# sonopi-dac-type2.net
KiCad netlist of a schematic drawn in EAGLE
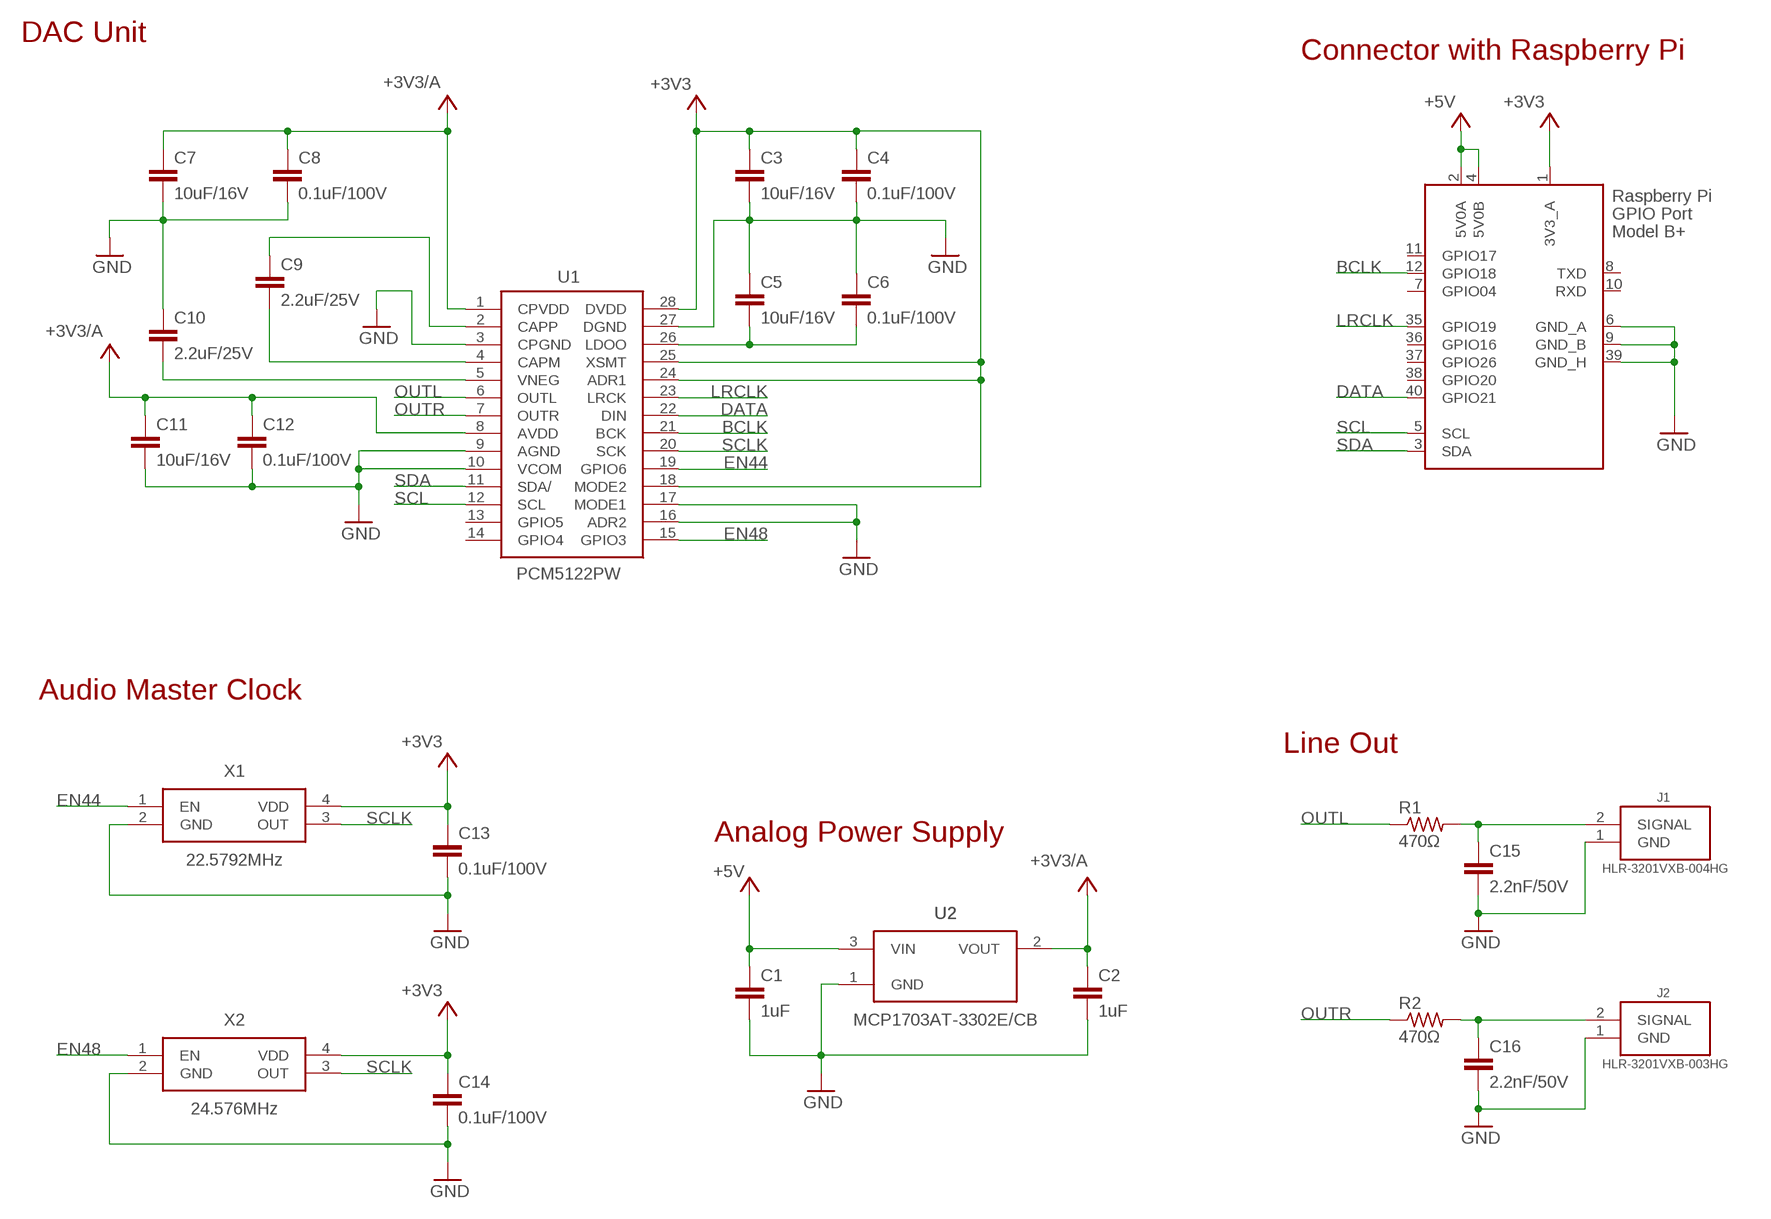
[diagram p0: schematic, sheet 1]

(export (version "E")
  (design (tool "Eeschema 10.0.6"))
  (components
    (comp (ref "C1")
      (value "1uF")
      (footprint "eagle-import:C0603")
      (libsource (lib "eagle-import") (part "C-EUC0603"))
    )
    (comp (ref "C2")
      (value "1uF")
      (footprint "eagle-import:C0603")
      (libsource (lib "eagle-import") (part "C-EUC0603"))
    )
    (comp (ref "C3")
      (value "10uF/16V")
      (footprint "eagle-import:C3216")
      (libsource (lib "eagle-import") (part "C-EUC3216"))
    )
    (comp (ref "C4")
      (value "0.1uF/100V")
      (footprint "eagle-import:C0603")
      (libsource (lib "eagle-import") (part "C-EUC0603"))
    )
    (comp (ref "C5")
      (value "10uF/16V")
      (footprint "eagle-import:C3216")
      (libsource (lib "eagle-import") (part "C-EUC3216"))
    )
    (comp (ref "C6")
      (value "0.1uF/100V")
      (footprint "eagle-import:C0603")
      (libsource (lib "eagle-import") (part "C-EUC0603"))
    )
    (comp (ref "C7")
      (value "10uF/16V")
      (footprint "eagle-import:C3216")
      (libsource (lib "eagle-import") (part "C-EUC3216"))
    )
    (comp (ref "C8")
      (value "0.1uF/100V")
      (footprint "eagle-import:C0603")
      (libsource (lib "eagle-import") (part "C-EUC0603"))
    )
    (comp (ref "C9")
      (value "2.2uF/25V")
      (footprint "eagle-import:C0805")
      (libsource (lib "eagle-import") (part "C-EUC0805"))
    )
    (comp (ref "C10")
      (value "2.2uF/25V")
      (footprint "eagle-import:C0805")
      (libsource (lib "eagle-import") (part "C-EUC0805"))
    )
    (comp (ref "C11")
      (value "10uF/16V")
      (footprint "eagle-import:C3216")
      (libsource (lib "eagle-import") (part "C-EUC3216"))
    )
    (comp (ref "C12")
      (value "0.1uF/100V")
      (footprint "eagle-import:C0603")
      (libsource (lib "eagle-import") (part "C-EUC0603"))
    )
    (comp (ref "C13")
      (value "0.1uF/100V")
      (footprint "eagle-import:C0603")
      (libsource (lib "eagle-import") (part "C-EUC0603"))
    )
    (comp (ref "C14")
      (value "0.1uF/100V")
      (footprint "eagle-import:C0603")
      (libsource (lib "eagle-import") (part "C-EUC0603"))
    )
    (comp (ref "C15")
      (value "2.2nF/50V")
      (footprint "eagle-import:C0603")
      (libsource (lib "eagle-import") (part "C-EUC0603"))
    )
    (comp (ref "C16")
      (value "2.2nF/50V")
      (footprint "eagle-import:C0603")
      (libsource (lib "eagle-import") (part "C-EUC0603"))
    )
    (comp (ref "J1")
      (value "HLR-3201VXB-004HG")
      (footprint "eagle-import:HLR-3201VXB")
      (libsource (lib "eagle-import") (part "1CH-RCA-HLR-3201VXB"))
    )
    (comp (ref "J2")
      (value "HLR-3201VXB-003HG")
      (footprint "eagle-import:HLR-3201VXB")
      (libsource (lib "eagle-import") (part "1CH-RCA-HLR-3201VXB"))
    )
    (comp (ref "J3")
      (value "RASPI_BOARD_B+#_ZERO")
      (footprint "eagle-import:RASPI_BOARD_B+HAT_ZERO")
      (libsource (lib "eagle-import") (part "RASPI_BOARD_B+#_ZERO"))
    )
    (comp (ref "R1")
      (value "470Ω")
      (footprint "eagle-import:R0603")
      (libsource (lib "eagle-import") (part "R-US_R0603"))
    )
    (comp (ref "R2")
      (value "470Ω")
      (footprint "eagle-import:R0603")
      (libsource (lib "eagle-import") (part "R-US_R0603"))
    )
    (comp (ref "U1")
      (value "PCM5122PW")
      (footprint "eagle-import:SOP65P640X120-28N")
      (fields (field (name "MOUSER_PART_NUMBER") "595-PCM5122PW") (field (name "RS_PART_NUMBER") "8143732P"))
      (libsource (lib "eagle-import") (part "PCM5122PW"))
    )
    (comp (ref "U2")
      (value "MCP1703AT-3302E/CB")
      (footprint "eagle-import:SOT23")
      (libsource (lib "eagle-import") (part "LDO-REGULATOR"))
    )
    (comp (ref "X1")
      (value "22.5792MHz")
      (footprint "eagle-import:3225-SMD-HS")
      (libsource (lib "eagle-import") (part "OSC-3225HS"))
    )
    (comp (ref "X2")
      (value "24.576MHz")
      (footprint "eagle-import:3225-SMD-HS")
      (libsource (lib "eagle-import") (part "OSC-3225HS"))
    )
  )
  (nets
    (net (code "1") (name "+3V3") (class "Default")
      (node (ref "C13") (pin "1") (pinfunction "1_1") (pintype "passive"))
      (node (ref "C14") (pin "1") (pinfunction "1_1") (pintype "passive"))
      (node (ref "C3") (pin "1") (pinfunction "1_1") (pintype "passive"))
      (node (ref "C4") (pin "1") (pinfunction "1_1") (pintype "passive"))
      (node (ref "J3") (pin "1") (pinfunction "3V3_A_1") (pintype "power_in"))
      (node (ref "U1") (pin "18") (pinfunction "MODE2_18") (pintype "bidirectional"))
      (node (ref "U1") (pin "24") (pinfunction "ADR1_24") (pintype "bidirectional"))
      (node (ref "U1") (pin "25") (pinfunction "XSMT_25") (pintype "bidirectional"))
      (node (ref "U1") (pin "28") (pinfunction "DVDD_28") (pintype "bidirectional"))
      (node (ref "X1") (pin "4") (pinfunction "VDD_4") (pintype "power_in"))
      (node (ref "X2") (pin "4") (pinfunction "VDD_4") (pintype "power_in"))
    )
    (net (code "2") (name "+3V3{slash}A") (class "Default")
      (node (ref "C11") (pin "1") (pinfunction "1_1") (pintype "passive"))
      (node (ref "C12") (pin "1") (pinfunction "1_1") (pintype "passive"))
      (node (ref "C2") (pin "1") (pinfunction "1_1") (pintype "passive"))
      (node (ref "C7") (pin "1") (pinfunction "1_1") (pintype "passive"))
      (node (ref "C8") (pin "1") (pinfunction "1_1") (pintype "passive"))
      (node (ref "U1") (pin "1") (pinfunction "CPVDD_1") (pintype "bidirectional"))
      (node (ref "U1") (pin "8") (pinfunction "AVDD_8") (pintype "bidirectional"))
      (node (ref "U2") (pin "2") (pinfunction "VOUT_2") (pintype "bidirectional"))
    )
    (net (code "3") (name "+5V") (class "Default")
      (node (ref "C1") (pin "1") (pinfunction "1_1") (pintype "passive"))
      (node (ref "J3") (pin "2") (pinfunction "5V0A_2") (pintype "power_in"))
      (node (ref "J3") (pin "4") (pinfunction "5V0B_4") (pintype "power_in"))
      (node (ref "U2") (pin "3") (pinfunction "VIN_3") (pintype "bidirectional"))
    )
    (net (code "4") (name "/BCLK") (class "Default")
      (node (ref "J3") (pin "12") (pinfunction "GPIO18_12") (pintype "bidirectional"))
      (node (ref "U1") (pin "21") (pinfunction "BCK_21") (pintype "bidirectional"))
    )
    (net (code "5") (name "/DATA") (class "Default")
      (node (ref "J3") (pin "40") (pinfunction "GPIO21_40") (pintype "bidirectional"))
      (node (ref "U1") (pin "22") (pinfunction "DIN_22") (pintype "bidirectional"))
    )
    (net (code "6") (name "/EN44") (class "Default")
      (node (ref "U1") (pin "19") (pinfunction "GPIO6_19") (pintype "bidirectional"))
      (node (ref "X1") (pin "1") (pinfunction "EN_1") (pintype "bidirectional"))
    )
    (net (code "7") (name "/EN48") (class "Default")
      (node (ref "U1") (pin "15") (pinfunction "GPIO3_15") (pintype "bidirectional"))
      (node (ref "X2") (pin "1") (pinfunction "EN_1") (pintype "bidirectional"))
    )
    (net (code "8") (name "/LRCLK") (class "Default")
      (node (ref "J3") (pin "35") (pinfunction "GPIO19_35") (pintype "bidirectional"))
      (node (ref "U1") (pin "23") (pinfunction "LRCK_23") (pintype "bidirectional"))
    )
    (net (code "9") (name "/OUTL") (class "Default")
      (node (ref "R1") (pin "1") (pinfunction "1_1") (pintype "passive"))
      (node (ref "U1") (pin "6") (pinfunction "OUTL_6") (pintype "bidirectional"))
    )
    (net (code "10") (name "/OUTR") (class "Default")
      (node (ref "R2") (pin "1") (pinfunction "1_1") (pintype "passive"))
      (node (ref "U1") (pin "7") (pinfunction "OUTR_7") (pintype "bidirectional"))
    )
    (net (code "11") (name "/SCL") (class "Default")
      (node (ref "J3") (pin "5") (pinfunction "SCL_5") (pintype "bidirectional"))
      (node (ref "U1") (pin "12") (pinfunction "SCL_12") (pintype "bidirectional"))
    )
    (net (code "12") (name "/SCLK") (class "Default")
      (node (ref "U1") (pin "20") (pinfunction "SCK_20") (pintype "bidirectional"))
      (node (ref "X1") (pin "3") (pinfunction "OUT_3") (pintype "bidirectional"))
      (node (ref "X2") (pin "3") (pinfunction "OUT_3") (pintype "bidirectional"))
    )
    (net (code "13") (name "/SDA") (class "Default")
      (node (ref "J3") (pin "3") (pinfunction "SDA_3") (pintype "bidirectional"))
      (node (ref "U1") (pin "11") (pinfunction "SDA/_11") (pintype "bidirectional"))
    )
    (net (code "14") (name "GND") (class "Default")
      (node (ref "C1") (pin "2") (pinfunction "2_2") (pintype "passive"))
      (node (ref "C10") (pin "1") (pinfunction "1_1") (pintype "passive"))
      (node (ref "C11") (pin "2") (pinfunction "2_2") (pintype "passive"))
      (node (ref "C12") (pin "2") (pinfunction "2_2") (pintype "passive"))
      (node (ref "C13") (pin "2") (pinfunction "2_2") (pintype "passive"))
      (node (ref "C14") (pin "2") (pinfunction "2_2") (pintype "passive"))
      (node (ref "C15") (pin "2") (pinfunction "2_2") (pintype "passive"))
      (node (ref "C16") (pin "2") (pinfunction "2_2") (pintype "passive"))
      (node (ref "C2") (pin "2") (pinfunction "2_2") (pintype "passive"))
      (node (ref "C3") (pin "2") (pinfunction "2_2") (pintype "passive"))
      (node (ref "C4") (pin "2") (pinfunction "2_2") (pintype "passive"))
      (node (ref "C5") (pin "1") (pinfunction "1_1") (pintype "passive"))
      (node (ref "C6") (pin "1") (pinfunction "1_1") (pintype "passive"))
      (node (ref "C7") (pin "2") (pinfunction "2_2") (pintype "passive"))
      (node (ref "C8") (pin "2") (pinfunction "2_2") (pintype "passive"))
      (node (ref "J1") (pin "1") (pinfunction "GND_1") (pintype "power_in"))
      (node (ref "J2") (pin "1") (pinfunction "GND_1") (pintype "power_in"))
      (node (ref "J3") (pin "39") (pinfunction "GND_H_39") (pintype "power_in"))
      (node (ref "J3") (pin "6") (pinfunction "GND_A_6") (pintype "power_in"))
      (node (ref "J3") (pin "9") (pinfunction "GND_B_9") (pintype "power_in"))
      (node (ref "U1") (pin "10") (pinfunction "VCOM_10") (pintype "bidirectional"))
      (node (ref "U1") (pin "16") (pinfunction "ADR2_16") (pintype "bidirectional"))
      (node (ref "U1") (pin "17") (pinfunction "MODE1_17") (pintype "bidirectional"))
      (node (ref "U1") (pin "27") (pinfunction "DGND_27") (pintype "bidirectional"))
      (node (ref "U1") (pin "3") (pinfunction "CPGND_3") (pintype "bidirectional"))
      (node (ref "U1") (pin "9") (pinfunction "AGND_9") (pintype "bidirectional"))
      (node (ref "U2") (pin "1") (pinfunction "GND_1") (pintype "bidirectional"))
      (node (ref "X1") (pin "2") (pinfunction "GND_2") (pintype "power_in"))
      (node (ref "X2") (pin "2") (pinfunction "GND_2") (pintype "power_in"))
    )
    (net (code "15") (name "Net-(J1-SIGNAL)") (class "Default")
      (node (ref "C15") (pin "1") (pinfunction "1_1") (pintype "passive"))
      (node (ref "J1") (pin "2") (pinfunction "SIGNAL_2") (pintype "bidirectional"))
      (node (ref "R1") (pin "2") (pinfunction "2_2") (pintype "passive"))
    )
    (net (code "16") (name "Net-(J2-SIGNAL)") (class "Default")
      (node (ref "C16") (pin "1") (pinfunction "1_1") (pintype "passive"))
      (node (ref "J2") (pin "2") (pinfunction "SIGNAL_2") (pintype "bidirectional"))
      (node (ref "R2") (pin "2") (pinfunction "2_2") (pintype "passive"))
    )
    (net (code "17") (name "Net-(U1-CAPM)") (class "Default")
      (node (ref "C9") (pin "2") (pinfunction "2_2") (pintype "passive"))
      (node (ref "U1") (pin "4") (pinfunction "CAPM_4") (pintype "bidirectional"))
    )
    (net (code "18") (name "Net-(U1-CAPP)") (class "Default")
      (node (ref "C9") (pin "1") (pinfunction "1_1") (pintype "passive"))
      (node (ref "U1") (pin "2") (pinfunction "CAPP_2") (pintype "bidirectional"))
    )
    (net (code "19") (name "Net-(U1-LDOO)") (class "Default")
      (node (ref "C5") (pin "2") (pinfunction "2_2") (pintype "passive"))
      (node (ref "C6") (pin "2") (pinfunction "2_2") (pintype "passive"))
      (node (ref "U1") (pin "26") (pinfunction "LDOO_26") (pintype "bidirectional"))
    )
    (net (code "20") (name "Net-(U1-VNEG)") (class "Default")
      (node (ref "C10") (pin "2") (pinfunction "2_2") (pintype "passive"))
      (node (ref "U1") (pin "5") (pinfunction "VNEG_5") (pintype "bidirectional"))
    )
    (net (code "21") (name "unconnected-(J3-GPIO04-Pad7)") (class "Default")
      (node (ref "J3") (pin "7") (pinfunction "GPIO04_7") (pintype "bidirectional"))
    )
    (net (code "22") (name "unconnected-(J3-GPIO16-Pad36)") (class "Default")
      (node (ref "J3") (pin "36") (pinfunction "GPIO16_36") (pintype "bidirectional"))
    )
    (net (code "23") (name "unconnected-(J3-GPIO17-Pad11)") (class "Default")
      (node (ref "J3") (pin "11") (pinfunction "GPIO17_11") (pintype "bidirectional"))
    )
    (net (code "24") (name "unconnected-(J3-GPIO20-Pad38)") (class "Default")
      (node (ref "J3") (pin "38") (pinfunction "GPIO20_38") (pintype "bidirectional"))
    )
    (net (code "25") (name "unconnected-(J3-GPIO26-Pad37)") (class "Default")
      (node (ref "J3") (pin "37") (pinfunction "GPIO26_37") (pintype "bidirectional"))
    )
    (net (code "26") (name "unconnected-(J3-RXD-Pad10)") (class "Default")
      (node (ref "J3") (pin "10") (pinfunction "RXD_10") (pintype "bidirectional"))
    )
    (net (code "27") (name "unconnected-(J3-TXD-Pad8)") (class "Default")
      (node (ref "J3") (pin "8") (pinfunction "TXD_8") (pintype "bidirectional"))
    )
    (net (code "28") (name "unconnected-(U1-GPIO4-Pad14)") (class "Default")
      (node (ref "U1") (pin "14") (pinfunction "GPIO4_14") (pintype "bidirectional"))
    )
    (net (code "29") (name "unconnected-(U1-GPIO5-Pad13)") (class "Default")
      (node (ref "U1") (pin "13") (pinfunction "GPIO5_13") (pintype "bidirectional"))
    )
  )
)
